# ConnectorsCircuit.net
KiCad netlist of a schematic drawn in Altium Designer
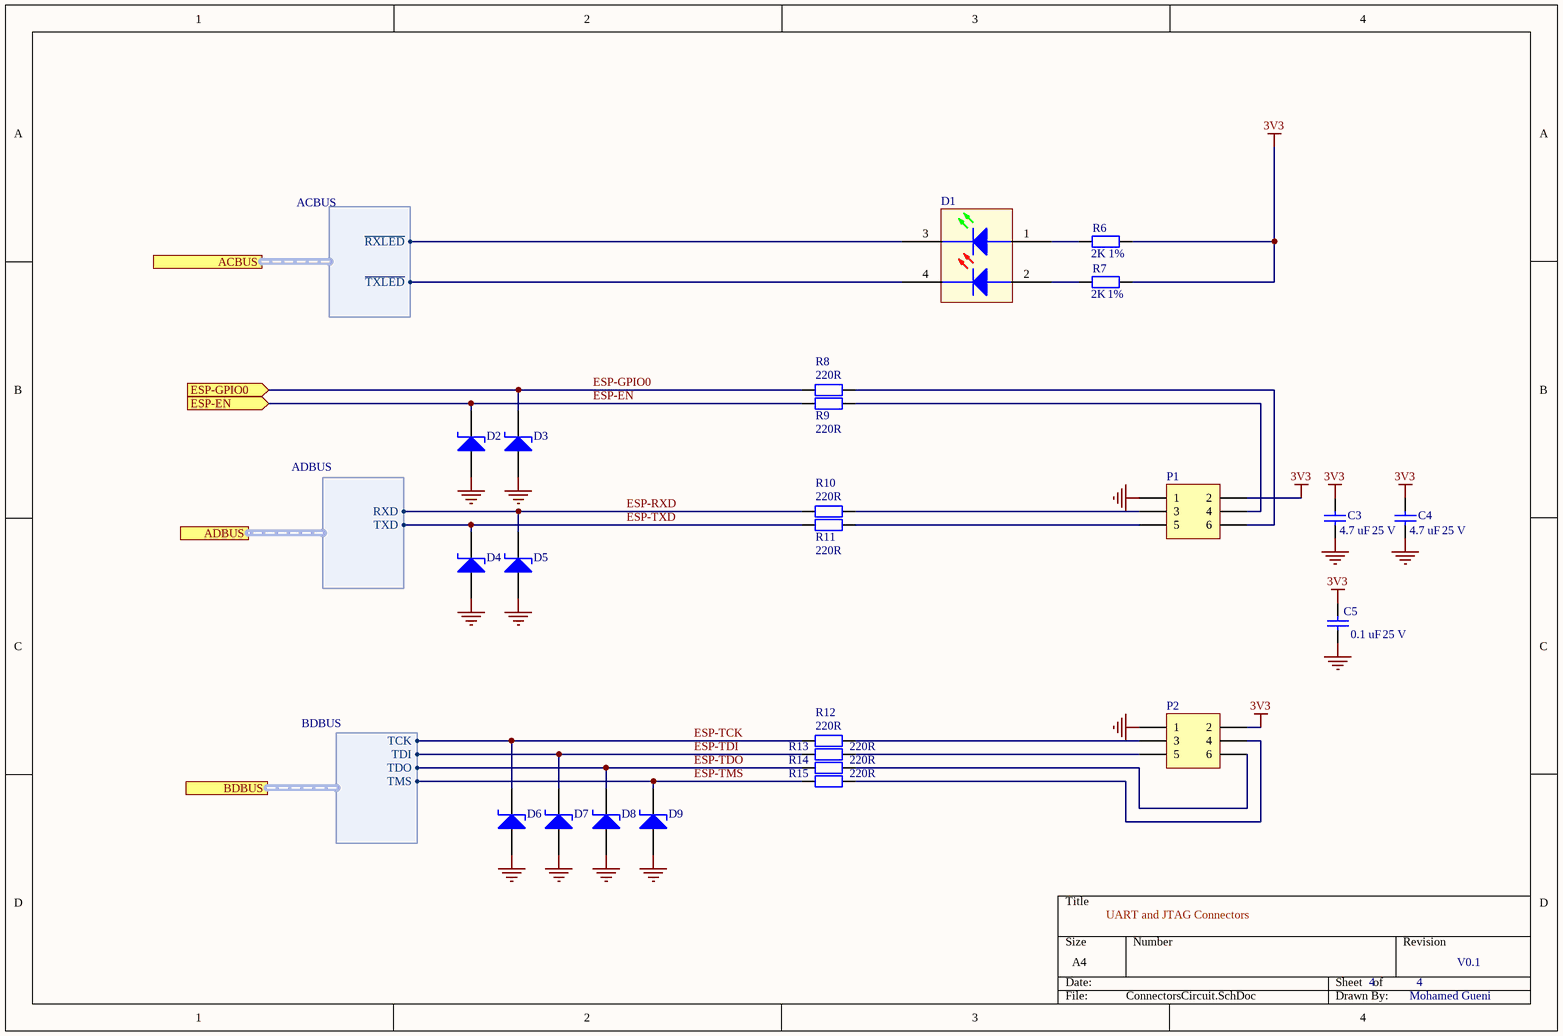
[diagram p0: ConnectorsCircuit.SchDoc]

(export (version "E")
  (design (tool "Eeschema 10.0.6"))
  (components
    (comp (ref "C3")
      (value "Capacitor")
      (footprint "CAP0603")
      (fields (field (name "VALUE 1") "4.7 uF") (field (name "VALUE 2") "25 V"))
      (libsource (lib "Database_Libs1") (part "Capacitor"))
    )
    (comp (ref "C4")
      (value "Capacitor")
      (footprint "CAP0603")
      (fields (field (name "VALUE 1") "4.7 uF") (field (name "VALUE 2") "25 V"))
      (libsource (lib "Database_Libs1") (part "Capacitor"))
    )
    (comp (ref "C5")
      (value "Capacitor")
      (footprint "CAP0603")
      (fields (field (name "VALUE 1") "0.1 uF") (field (name "VALUE 2") "25 V"))
      (libsource (lib "Database_Libs1") (part "Capacitor"))
    )
    (comp (ref "D1")
      (value "LTST-C155KGJRKT")
      (footprint "LTSTC155KGJRKT")
      (description "LTST-C155KGJRKT, Lite-On 571 / 631 nm 2 Green & Red LED, 4-Pin 3125 (1210) SMD package")
      (fields (field (name "MOUSER PART NUMBER") "859-LTST-C155KGJRKT"))
      (libsource (lib "Database_Libs1") (part "LTST-C155KGJRKT"))
    )
    (comp (ref "D2")
      (value "ESD8351HT1G")
      (footprint "SOD-323")
      (description "TVS Unidirectionel")
      (libsource (lib "Database_Libs1") (part "TVS_U"))
    )
    (comp (ref "D3")
      (value "ESD8351HT1G")
      (footprint "SOD-323")
      (description "TVS Unidirectionel")
      (libsource (lib "Database_Libs1") (part "TVS_U"))
    )
    (comp (ref "D4")
      (value "ESD8351HT1G")
      (footprint "SOD-323")
      (description "TVS Unidirectionel")
      (libsource (lib "Database_Libs1") (part "TVS_U"))
    )
    (comp (ref "D5")
      (value "ESD8351HT1G")
      (footprint "SOD-323")
      (description "TVS Unidirectionel")
      (libsource (lib "Database_Libs1") (part "TVS_U"))
    )
    (comp (ref "D6")
      (value "ESD8351HT1G")
      (footprint "SOD-323")
      (description "TVS Unidirectionel")
      (libsource (lib "Database_Libs1") (part "TVS_U"))
    )
    (comp (ref "D7")
      (value "ESD8351HT1G")
      (footprint "SOD-323")
      (description "TVS Unidirectionel")
      (libsource (lib "Database_Libs1") (part "TVS_U"))
    )
    (comp (ref "D8")
      (value "ESD8351HT1G")
      (footprint "SOD-323")
      (description "TVS Unidirectionel")
      (libsource (lib "Database_Libs1") (part "TVS_U"))
    )
    (comp (ref "D9")
      (value "ESD8351HT1G")
      (footprint "SOD-323")
      (description "TVS Unidirectionel")
      (libsource (lib "Database_Libs1") (part "TVS_U"))
    )
    (comp (ref "P1")
      (value "Header 3X2")
      (footprint "SHDR6W75P200_2X3_865X640X650P")
      (description "Header, 3-Pin, Dual row")
      (fields (field (name "PUBLISHER") "Altium Limited"))
      (libsource (lib "Database_Libs1") (part "Header 3X2"))
    )
    (comp (ref "P2")
      (value "Header 3X2")
      (footprint "SHDR6W75P200_2X3_865X640X650P")
      (description "Header, 3-Pin, Dual row")
      (fields (field (name "PUBLISHER") "Altium Limited"))
      (libsource (lib "Database_Libs1") (part "Header 3X2"))
    )
    (comp (ref "R6")
      (value "Resistor")
      (footprint "RESC2012X65N2k")
      (fields (field (name "VALUE 1") "2K") (field (name "TOL") "1%"))
      (libsource (lib "Database_Libs1") (part "Resistor"))
    )
    (comp (ref "R7")
      (value "Resistor")
      (footprint "RESC2012X65N2k")
      (fields (field (name "VALUE 1") "2K") (field (name "TOL") "1%"))
      (libsource (lib "Database_Libs1") (part "Resistor"))
    )
    (comp (ref "R8")
      (value "Resistor")
      (footprint "RES0603")
      (fields (field (name "VALUE 1") "220R"))
      (libsource (lib "Database_Libs1") (part "Resistor"))
    )
    (comp (ref "R9")
      (value "Resistor")
      (footprint "RES0603")
      (fields (field (name "VALUE 1") "220R"))
      (libsource (lib "Database_Libs1") (part "Resistor"))
    )
    (comp (ref "R10")
      (value "Resistor")
      (footprint "RES0603")
      (fields (field (name "VALUE 1") "220R"))
      (libsource (lib "Database_Libs1") (part "Resistor"))
    )
    (comp (ref "R11")
      (value "Resistor")
      (footprint "RES0603")
      (fields (field (name "VALUE 1") "220R"))
      (libsource (lib "Database_Libs1") (part "Resistor"))
    )
    (comp (ref "R12")
      (value "Resistor")
      (footprint "RES0603")
      (fields (field (name "VALUE 1") "220R"))
      (libsource (lib "Database_Libs1") (part "Resistor"))
    )
    (comp (ref "R13")
      (value "Resistor")
      (footprint "RES0603")
      (fields (field (name "VALUE 1") "220R"))
      (libsource (lib "Database_Libs1") (part "Resistor"))
    )
    (comp (ref "R14")
      (value "Resistor")
      (footprint "RES0603")
      (fields (field (name "VALUE 1") "220R"))
      (libsource (lib "Database_Libs1") (part "Resistor"))
    )
    (comp (ref "R15")
      (value "Resistor")
      (footprint "RES0603")
      (fields (field (name "VALUE 1") "220R"))
      (libsource (lib "Database_Libs1") (part "Resistor"))
    )
  )
  (nets
    (net (code "4") (name "/ESP-EN") (class "Default")
      (node (ref "D2") (pin "2") (pinfunction "K1A2_2") (pintype "passive"))
      (node (ref "R9") (pin "1") (pinfunction "1_1") (pintype "passive"))
    )
    (net (code "5") (name "/ESP-GPIO0") (class "Default")
      (node (ref "D3") (pin "2") (pinfunction "K1A2_2") (pintype "passive"))
      (node (ref "R8") (pin "1") (pinfunction "1_1") (pintype "passive"))
    )
    (net (code "6") (name "/ESP-RXD") (class "Default")
      (node (ref "D5") (pin "2") (pinfunction "K1A2_2") (pintype "passive"))
      (node (ref "R10") (pin "1") (pinfunction "1_1") (pintype "passive"))
    )
    (net (code "7") (name "/ESP-TCK") (class "Default")
      (node (ref "D6") (pin "2") (pinfunction "K1A2_2") (pintype "passive"))
      (node (ref "R12") (pin "1") (pinfunction "1_1") (pintype "passive"))
    )
    (net (code "8") (name "/ESP-TDI") (class "Default")
      (node (ref "D7") (pin "2") (pinfunction "K1A2_2") (pintype "passive"))
      (node (ref "R13") (pin "1") (pinfunction "1_1") (pintype "passive"))
    )
    (net (code "9") (name "/ESP-TDO") (class "Default")
      (node (ref "D8") (pin "2") (pinfunction "K1A2_2") (pintype "passive"))
      (node (ref "R14") (pin "1") (pinfunction "1_1") (pintype "passive"))
    )
    (net (code "10") (name "/ESP-TMS") (class "Default")
      (node (ref "D9") (pin "2") (pinfunction "K1A2_2") (pintype "passive"))
      (node (ref "R15") (pin "1") (pinfunction "1_1") (pintype "passive"))
    )
    (net (code "11") (name "/ESP-TXD") (class "Default")
      (node (ref "D4") (pin "2") (pinfunction "K1A2_2") (pintype "passive"))
      (node (ref "R11") (pin "1") (pinfunction "1_1") (pintype "passive"))
    )
    (net (code "15") (name "/~{RXLED}") (class "Default")
      (node (ref "D1") (pin "3") (pinfunction "3_3") (pintype "passive"))
    )
    (net (code "16") (name "/~{TXLED}") (class "Default")
      (node (ref "D1") (pin "4") (pinfunction "4_4") (pintype "passive"))
    )
    (net (code "17") (name "3V3") (class "Default")
      (node (ref "C3") (pin "2") (pinfunction "2_2") (pintype "passive"))
      (node (ref "C4") (pin "2") (pinfunction "2_2") (pintype "passive"))
      (node (ref "C5") (pin "2") (pinfunction "2_2") (pintype "passive"))
      (node (ref "P1") (pin "2") (pinfunction "2_2") (pintype "passive"))
      (node (ref "P2") (pin "2") (pinfunction "2_2") (pintype "passive"))
      (node (ref "R6") (pin "2") (pinfunction "2_2") (pintype "passive"))
      (node (ref "R7") (pin "2") (pinfunction "2_2") (pintype "passive"))
    )
    (net (code "18") (name "GND") (class "Default")
      (node (ref "C3") (pin "1") (pinfunction "1_1") (pintype "passive"))
      (node (ref "C4") (pin "1") (pinfunction "1_1") (pintype "passive"))
      (node (ref "C5") (pin "1") (pinfunction "1_1") (pintype "passive"))
      (node (ref "D2") (pin "1") (pinfunction "1_1") (pintype "passive"))
      (node (ref "D3") (pin "1") (pinfunction "1_1") (pintype "passive"))
      (node (ref "D4") (pin "1") (pinfunction "1_1") (pintype "passive"))
      (node (ref "D5") (pin "1") (pinfunction "1_1") (pintype "passive"))
      (node (ref "D6") (pin "1") (pinfunction "1_1") (pintype "passive"))
      (node (ref "D7") (pin "1") (pinfunction "1_1") (pintype "passive"))
      (node (ref "D8") (pin "1") (pinfunction "1_1") (pintype "passive"))
      (node (ref "D9") (pin "1") (pinfunction "1_1") (pintype "passive"))
      (node (ref "P1") (pin "1") (pinfunction "1_1") (pintype "passive"))
      (node (ref "P2") (pin "1") (pinfunction "1_1") (pintype "passive"))
    )
    (net (code "19") (name "Net-(D1-Pad1)") (class "Default")
      (node (ref "D1") (pin "1") (pinfunction "1_1") (pintype "passive"))
      (node (ref "R6") (pin "1") (pinfunction "1_1") (pintype "passive"))
    )
    (net (code "20") (name "Net-(D1-Pad2)") (class "Default")
      (node (ref "D1") (pin "2") (pinfunction "2_2") (pintype "passive"))
      (node (ref "R7") (pin "1") (pinfunction "1_1") (pintype "passive"))
    )
    (net (code "21") (name "Net-(P1-Pad3)") (class "Default")
      (node (ref "P1") (pin "3") (pinfunction "3_3") (pintype "passive"))
      (node (ref "R10") (pin "2") (pinfunction "2_2") (pintype "passive"))
    )
    (net (code "22") (name "Net-(P1-Pad4)") (class "Default")
      (node (ref "P1") (pin "4") (pinfunction "4_4") (pintype "passive"))
      (node (ref "R9") (pin "2") (pinfunction "2_2") (pintype "passive"))
    )
    (net (code "23") (name "Net-(P1-Pad5)") (class "Default")
      (node (ref "P1") (pin "5") (pinfunction "5_5") (pintype "passive"))
      (node (ref "R11") (pin "2") (pinfunction "2_2") (pintype "passive"))
    )
    (net (code "24") (name "Net-(P1-Pad6)") (class "Default")
      (node (ref "P1") (pin "6") (pinfunction "6_6") (pintype "passive"))
      (node (ref "R8") (pin "2") (pinfunction "2_2") (pintype "passive"))
    )
    (net (code "25") (name "Net-(P2-Pad3)") (class "Default")
      (node (ref "P2") (pin "3") (pinfunction "3_3") (pintype "passive"))
      (node (ref "R12") (pin "2") (pinfunction "2_2") (pintype "passive"))
    )
    (net (code "26") (name "Net-(P2-Pad4)") (class "Default")
      (node (ref "P2") (pin "4") (pinfunction "4_4") (pintype "passive"))
      (node (ref "R15") (pin "2") (pinfunction "2_2") (pintype "passive"))
    )
    (net (code "27") (name "Net-(P2-Pad5)") (class "Default")
      (node (ref "P2") (pin "5") (pinfunction "5_5") (pintype "passive"))
      (node (ref "R13") (pin "2") (pinfunction "2_2") (pintype "passive"))
    )
    (net (code "28") (name "Net-(P2-Pad6)") (class "Default")
      (node (ref "P2") (pin "6") (pinfunction "6_6") (pintype "passive"))
      (node (ref "R14") (pin "2") (pinfunction "2_2") (pintype "passive"))
    )
  )
)
